# Door_Position_Monitoring.net
KiCad netlist of a schematic drawn in Altium Designer
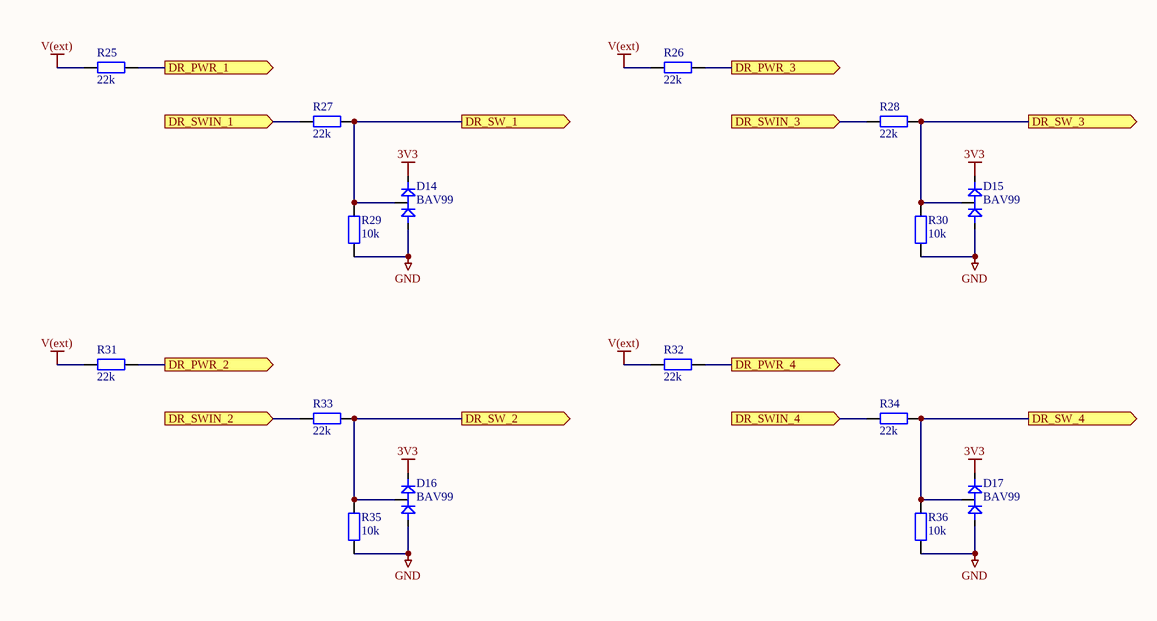
[diagram p0: Door Position Monitoring.SchDoc]

(export (version "E")
  (design (tool "Eeschema 10.0.6"))
  (components
    (comp (ref "D14")
      (value "BAV99")
      (footprint "ONSC-SOT-23-3-318-08_V")
      (description "Dual Series Switching Diodes, 3-Pin SOT-23, Pb-Free, Tape and Reel")
      (libsource (lib "FavoritesLibrary") (part "ONSC-D-A1K2C3-3"))
    )
    (comp (ref "D15")
      (value "BAV99")
      (footprint "ONSC-SOT-23-3-318-08_V")
      (description "Dual Series Switching Diodes, 3-Pin SOT-23, Pb-Free, Tape and Reel")
      (libsource (lib "FavoritesLibrary") (part "ONSC-D-A1K2C3-3"))
    )
    (comp (ref "D16")
      (value "BAV99")
      (footprint "ONSC-SOT-23-3-318-08_V")
      (description "Dual Series Switching Diodes, 3-Pin SOT-23, Pb-Free, Tape and Reel")
      (libsource (lib "FavoritesLibrary") (part "ONSC-D-A1K2C3-3"))
    )
    (comp (ref "D17")
      (value "BAV99")
      (footprint "ONSC-SOT-23-3-318-08_V")
      (description "Dual Series Switching Diodes, 3-Pin SOT-23, Pb-Free, Tape and Reel")
      (libsource (lib "FavoritesLibrary") (part "ONSC-D-A1K2C3-3"))
    )
    (comp (ref "R25")
      (value "22k")
      (footprint "PCB-3652081-2")
      (description "GENERIC 0805 RESISTOR")
      (libsource (lib "FavoritesLibrary") (part "SYM-rprrpiwz7au7w5x5ojb2-1"))
    )
    (comp (ref "R26")
      (value "22k")
      (footprint "PCB-3652081-2")
      (description "GENERIC 0805 RESISTOR")
      (libsource (lib "FavoritesLibrary") (part "SYM-rprrpiwz7au7w5x5ojb2-1"))
    )
    (comp (ref "R27")
      (value "22k")
      (footprint "PCB-3652081-2")
      (description "GENERIC 0805 RESISTOR")
      (libsource (lib "FavoritesLibrary") (part "SYM-rprrpiwz7au7w5x5ojb2-1"))
    )
    (comp (ref "R28")
      (value "22k")
      (footprint "PCB-3652081-2")
      (description "GENERIC 0805 RESISTOR")
      (libsource (lib "FavoritesLibrary") (part "SYM-rprrpiwz7au7w5x5ojb2-1"))
    )
    (comp (ref "R29")
      (value "10k")
      (footprint "PCB-3652081-2")
      (description "GENERIC 0805 RESISTOR")
      (libsource (lib "FavoritesLibrary") (part "SYM-rprrpiwz7au7w5x5ojb2-1"))
    )
    (comp (ref "R30")
      (value "10k")
      (footprint "PCB-3652081-2")
      (description "GENERIC 0805 RESISTOR")
      (libsource (lib "FavoritesLibrary") (part "SYM-rprrpiwz7au7w5x5ojb2-1"))
    )
    (comp (ref "R31")
      (value "22k")
      (footprint "PCB-3652081-2")
      (description "GENERIC 0805 RESISTOR")
      (libsource (lib "FavoritesLibrary") (part "SYM-rprrpiwz7au7w5x5ojb2-1"))
    )
    (comp (ref "R32")
      (value "22k")
      (footprint "PCB-3652081-2")
      (description "GENERIC 0805 RESISTOR")
      (libsource (lib "FavoritesLibrary") (part "SYM-rprrpiwz7au7w5x5ojb2-1"))
    )
    (comp (ref "R33")
      (value "22k")
      (footprint "PCB-3652081-2")
      (description "GENERIC 0805 RESISTOR")
      (libsource (lib "FavoritesLibrary") (part "SYM-rprrpiwz7au7w5x5ojb2-1"))
    )
    (comp (ref "R34")
      (value "22k")
      (footprint "PCB-3652081-2")
      (description "GENERIC 0805 RESISTOR")
      (libsource (lib "FavoritesLibrary") (part "SYM-rprrpiwz7au7w5x5ojb2-1"))
    )
    (comp (ref "R35")
      (value "10k")
      (footprint "PCB-3652081-2")
      (description "GENERIC 0805 RESISTOR")
      (libsource (lib "FavoritesLibrary") (part "SYM-rprrpiwz7au7w5x5ojb2-1"))
    )
    (comp (ref "R36")
      (value "10k")
      (footprint "PCB-3652081-2")
      (description "GENERIC 0805 RESISTOR")
      (libsource (lib "FavoritesLibrary") (part "SYM-rprrpiwz7au7w5x5ojb2-1"))
    )
  )
  (nets
    (net (code "1") (name "/DR_PWR_1") (class "Default")
      (node (ref "R25") (pin "1") (pinfunction "1_1") (pintype "passive"))
    )
    (net (code "2") (name "/DR_PWR_2") (class "Default")
      (node (ref "R31") (pin "1") (pinfunction "1_1") (pintype "passive"))
    )
    (net (code "3") (name "/DR_PWR_3") (class "Default")
      (node (ref "R26") (pin "1") (pinfunction "1_1") (pintype "passive"))
    )
    (net (code "4") (name "/DR_PWR_4") (class "Default")
      (node (ref "R32") (pin "1") (pinfunction "1_1") (pintype "passive"))
    )
    (net (code "5") (name "/DR_SWIN_1") (class "Default")
      (node (ref "R27") (pin "2") (pinfunction "2_2") (pintype "passive"))
    )
    (net (code "6") (name "/DR_SWIN_2") (class "Default")
      (node (ref "R33") (pin "2") (pinfunction "2_2") (pintype "passive"))
    )
    (net (code "7") (name "/DR_SWIN_3") (class "Default")
      (node (ref "R28") (pin "2") (pinfunction "2_2") (pintype "passive"))
    )
    (net (code "8") (name "/DR_SWIN_4") (class "Default")
      (node (ref "R34") (pin "2") (pinfunction "2_2") (pintype "passive"))
    )
    (net (code "9") (name "/DR_SW_1") (class "Default")
      (node (ref "D14") (pin "3") (pinfunction "K/A_3") (pintype "passive"))
      (node (ref "R27") (pin "1") (pinfunction "1_1") (pintype "passive"))
      (node (ref "R29") (pin "2") (pinfunction "2_2") (pintype "passive"))
    )
    (net (code "10") (name "/DR_SW_2") (class "Default")
      (node (ref "D16") (pin "3") (pinfunction "K/A_3") (pintype "passive"))
      (node (ref "R33") (pin "1") (pinfunction "1_1") (pintype "passive"))
      (node (ref "R35") (pin "2") (pinfunction "2_2") (pintype "passive"))
    )
    (net (code "11") (name "/DR_SW_3") (class "Default")
      (node (ref "D15") (pin "3") (pinfunction "K/A_3") (pintype "passive"))
      (node (ref "R28") (pin "1") (pinfunction "1_1") (pintype "passive"))
      (node (ref "R30") (pin "2") (pinfunction "2_2") (pintype "passive"))
    )
    (net (code "12") (name "/DR_SW_4") (class "Default")
      (node (ref "D17") (pin "3") (pinfunction "K/A_3") (pintype "passive"))
      (node (ref "R34") (pin "1") (pinfunction "1_1") (pintype "passive"))
      (node (ref "R36") (pin "2") (pinfunction "2_2") (pintype "passive"))
    )
    (net (code "13") (name "3V3") (class "Default")
      (node (ref "D14") (pin "2") (pinfunction "K_2") (pintype "passive"))
      (node (ref "D15") (pin "2") (pinfunction "K_2") (pintype "passive"))
      (node (ref "D16") (pin "2") (pinfunction "K_2") (pintype "passive"))
      (node (ref "D17") (pin "2") (pinfunction "K_2") (pintype "passive"))
    )
    (net (code "14") (name "GND") (class "Default")
      (node (ref "D14") (pin "1") (pinfunction "A_1") (pintype "passive"))
      (node (ref "D15") (pin "1") (pinfunction "A_1") (pintype "passive"))
      (node (ref "D16") (pin "1") (pinfunction "A_1") (pintype "passive"))
      (node (ref "D17") (pin "1") (pinfunction "A_1") (pintype "passive"))
      (node (ref "R29") (pin "1") (pinfunction "1_1") (pintype "passive"))
      (node (ref "R30") (pin "1") (pinfunction "1_1") (pintype "passive"))
      (node (ref "R35") (pin "1") (pinfunction "1_1") (pintype "passive"))
      (node (ref "R36") (pin "1") (pinfunction "1_1") (pintype "passive"))
    )
    (net (code "15") (name "V(ext)") (class "Default")
      (node (ref "R25") (pin "2") (pinfunction "2_2") (pintype "passive"))
      (node (ref "R26") (pin "2") (pinfunction "2_2") (pintype "passive"))
      (node (ref "R31") (pin "2") (pinfunction "2_2") (pintype "passive"))
      (node (ref "R32") (pin "2") (pinfunction "2_2") (pintype "passive"))
    )
  )
)
